# LeCoolStick-MainShield_v1.net
KiCad netlist of a schematic drawn in EAGLE
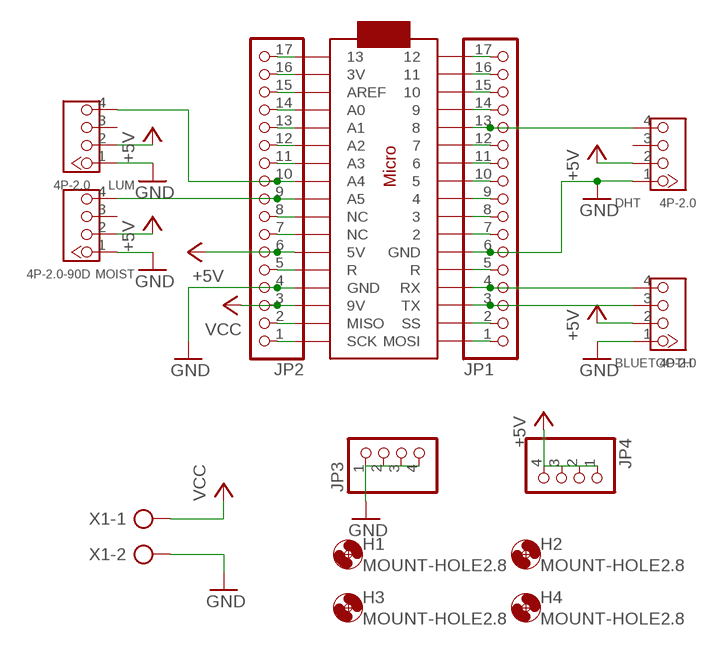
[diagram p0: schematic, sheet 1]

(export (version "E")
  (design (tool "Eeschema 10.0.6"))
  (components
    (comp (ref "BLUETOOTH")
      (value "4P-2.0")
      (footprint "eagle-import:HW4-2.0")
      (libsource (lib "eagle-import") (part "GROVE-CONNECTOR-DIP(4P-2.0)"))
    )
    (comp (ref "DHT")
      (value "4P-2.0")
      (footprint "eagle-import:HW4-2.0")
      (libsource (lib "eagle-import") (part "GROVE-CONNECTOR-DIP(4P-2.0)"))
    )
    (comp (ref "H1")
      (value "MOUNT-HOLE2.8")
      (footprint "eagle-import:2,8")
      (libsource (lib "eagle-import") (part "MOUNT-HOLE2.8"))
    )
    (comp (ref "H2")
      (value "MOUNT-HOLE2.8")
      (footprint "eagle-import:2,8")
      (libsource (lib "eagle-import") (part "MOUNT-HOLE2.8"))
    )
    (comp (ref "H3")
      (value "MOUNT-HOLE2.8")
      (footprint "eagle-import:2,8")
      (libsource (lib "eagle-import") (part "MOUNT-HOLE2.8"))
    )
    (comp (ref "H4")
      (value "MOUNT-HOLE2.8")
      (footprint "eagle-import:2,8")
      (libsource (lib "eagle-import") (part "MOUNT-HOLE2.8"))
    )
    (comp (ref "JP1")
      (value "PINHD-1X17")
      (footprint "eagle-import:1X17")
      (libsource (lib "eagle-import") (part "PINHD-1X17"))
    )
    (comp (ref "JP2")
      (value "PINHD-1X17")
      (footprint "eagle-import:1X17")
      (libsource (lib "eagle-import") (part "PINHD-1X17"))
    )
    (comp (ref "JP3")
      (value "PINHD-1X4")
      (footprint "eagle-import:1X04")
      (libsource (lib "eagle-import") (part "PINHD-1X4"))
    )
    (comp (ref "JP4")
      (value "PINHD-1X4")
      (footprint "eagle-import:1X04")
      (libsource (lib "eagle-import") (part "PINHD-1X4"))
    )
    (comp (ref "LUM")
      (value "4P-2.0")
      (footprint "eagle-import:HW4-2.0")
      (libsource (lib "eagle-import") (part "GROVE-CONNECTOR-DIP(4P-2.0)"))
    )
    (comp (ref "MOIST")
      (value "4P-2.0-90D")
      (footprint "eagle-import:HW4-2.0-90D")
      (libsource (lib "eagle-import") (part "GROVE-CONNECTOR-DIP-90D(4P-2.0)"))
    )
    (comp (ref "U$1")
      (value "ARDUINOMICRO")
      (footprint "eagle-import:ARDUINOMICRO")
      (libsource (lib "eagle-import") (part "ARDUINOMICRO"))
    )
    (comp (ref "X1")
      (value "AK500/2")
      (footprint "eagle-import:AK500_2")
      (libsource (lib "eagle-import") (part "AK500/2"))
    )
  )
  (nets
    (net (code "1") (name "+5V") (class "Default")
      (node (ref "BLUETOOTH") (pin "2") (pinfunction "2_2") (pintype "bidirectional"))
      (node (ref "DHT") (pin "2") (pinfunction "2_2") (pintype "bidirectional"))
      (node (ref "JP2") (pin "6") (pinfunction "6_6") (pintype "passive"))
      (node (ref "JP4") (pin "1") (pinfunction "1_1") (pintype "passive"))
      (node (ref "JP4") (pin "2") (pinfunction "2_2") (pintype "passive"))
      (node (ref "JP4") (pin "3") (pinfunction "3_3") (pintype "passive"))
      (node (ref "JP4") (pin "4") (pinfunction "4_4") (pintype "passive"))
      (node (ref "LUM") (pin "2") (pinfunction "2_2") (pintype "bidirectional"))
      (node (ref "MOIST") (pin "2") (pinfunction "2_2") (pintype "bidirectional"))
      (node (ref "U$1") (pin "P$23") (pinfunction "5V_P$23") (pintype "bidirectional"))
    )
    (net (code "2") (name "GND") (class "Default")
      (node (ref "BLUETOOTH") (pin "1") (pinfunction "1_1") (pintype "bidirectional"))
      (node (ref "DHT") (pin "1") (pinfunction "1_1") (pintype "bidirectional"))
      (node (ref "JP1") (pin "6") (pinfunction "6_6") (pintype "passive"))
      (node (ref "JP2") (pin "4") (pinfunction "4_4") (pintype "passive"))
      (node (ref "JP3") (pin "1") (pinfunction "1_1") (pintype "passive"))
      (node (ref "JP3") (pin "2") (pinfunction "2_2") (pintype "passive"))
      (node (ref "JP3") (pin "3") (pinfunction "3_3") (pintype "passive"))
      (node (ref "JP3") (pin "4") (pinfunction "4_4") (pintype "passive"))
      (node (ref "LUM") (pin "1") (pinfunction "1_1") (pintype "bidirectional"))
      (node (ref "MOIST") (pin "1") (pinfunction "1_1") (pintype "bidirectional"))
      (node (ref "U$1") (pin "P$12") (pinfunction "GND_P$12") (pintype "bidirectional"))
      (node (ref "U$1") (pin "P$21") (pinfunction "GND_P$21") (pintype "bidirectional"))
      (node (ref "X1") (pin "2") (pinfunction "KL_2") (pintype "passive"))
    )
    (net (code "3") (name "Net-(JP1-Pad5)") (class "Default")
      (node (ref "JP1") (pin "5") (pinfunction "5_5") (pintype "passive"))
      (node (ref "U$1") (pin "P$22") (pinfunction "R_P$22") (pintype "bidirectional"))
    )
    (net (code "4") (name "Net-(JP2-Pad5)") (class "Default")
      (node (ref "JP2") (pin "5") (pinfunction "5_5") (pintype "passive"))
      (node (ref "U$1") (pin "P$13") (pinfunction "R_P$13") (pintype "bidirectional"))
    )
    (net (code "5") (name "Net-(JP2-Pad7)") (class "Default")
      (node (ref "JP2") (pin "7") (pinfunction "7_7") (pintype "passive"))
      (node (ref "U$1") (pin "P$24") (pinfunction "NC_P$24") (pintype "bidirectional"))
    )
    (net (code "6") (name "Net-(JP2-Pad8)") (class "Default")
      (node (ref "JP2") (pin "8") (pinfunction "8_8") (pintype "passive"))
      (node (ref "U$1") (pin "P$25") (pinfunction "NC_P$25") (pintype "bidirectional"))
    )
    (net (code "7") (name "Net-(U$1-2)") (class "Default")
      (node (ref "JP1") (pin "7") (pinfunction "7_7") (pintype "passive"))
      (node (ref "U$1") (pin "P$11") (pinfunction "2_P$11") (pintype "bidirectional"))
    )
    (net (code "8") (name "Net-(U$1-3)") (class "Default")
      (node (ref "JP1") (pin "8") (pinfunction "8_8") (pintype "passive"))
      (node (ref "U$1") (pin "P$10") (pinfunction "3_P$10") (pintype "bidirectional"))
    )
    (net (code "9") (name "Net-(U$1-3V)") (class "Default")
      (node (ref "JP2") (pin "16") (pinfunction "16_16") (pintype "passive"))
      (node (ref "U$1") (pin "P$33") (pinfunction "3V_P$33") (pintype "bidirectional"))
    )
    (net (code "10") (name "Net-(U$1-4)") (class "Default")
      (node (ref "JP1") (pin "9") (pinfunction "9_9") (pintype "passive"))
      (node (ref "U$1") (pin "P$9") (pinfunction "4_P$9") (pintype "bidirectional"))
    )
    (net (code "11") (name "Net-(U$1-5)") (class "Default")
      (node (ref "JP1") (pin "10") (pinfunction "10_10") (pintype "passive"))
      (node (ref "U$1") (pin "P$8") (pinfunction "5_P$8") (pintype "bidirectional"))
    )
    (net (code "12") (name "Net-(U$1-6)") (class "Default")
      (node (ref "JP1") (pin "11") (pinfunction "11_11") (pintype "passive"))
      (node (ref "U$1") (pin "P$7") (pinfunction "6_P$7") (pintype "bidirectional"))
    )
    (net (code "13") (name "Net-(U$1-7)") (class "Default")
      (node (ref "JP1") (pin "12") (pinfunction "12_12") (pintype "passive"))
      (node (ref "U$1") (pin "P$6") (pinfunction "7_P$6") (pintype "bidirectional"))
    )
    (net (code "14") (name "Net-(U$1-8)") (class "Default")
      (node (ref "DHT") (pin "4") (pinfunction "4_4") (pintype "bidirectional"))
      (node (ref "JP1") (pin "13") (pinfunction "13_13") (pintype "passive"))
      (node (ref "U$1") (pin "P$5") (pinfunction "8_P$5") (pintype "bidirectional"))
    )
    (net (code "15") (name "Net-(U$1-9)") (class "Default")
      (node (ref "JP1") (pin "14") (pinfunction "14_14") (pintype "passive"))
      (node (ref "U$1") (pin "P$4") (pinfunction "9_P$4") (pintype "bidirectional"))
    )
    (net (code "16") (name "Net-(U$1-10)") (class "Default")
      (node (ref "JP1") (pin "15") (pinfunction "15_15") (pintype "passive"))
      (node (ref "U$1") (pin "P$3") (pinfunction "10_P$3") (pintype "bidirectional"))
    )
    (net (code "17") (name "Net-(U$1-11)") (class "Default")
      (node (ref "JP1") (pin "16") (pinfunction "16_16") (pintype "passive"))
      (node (ref "U$1") (pin "P$2") (pinfunction "11_P$2") (pintype "bidirectional"))
    )
    (net (code "18") (name "Net-(U$1-12)") (class "Default")
      (node (ref "JP1") (pin "17") (pinfunction "17_17") (pintype "passive"))
      (node (ref "U$1") (pin "P$1") (pinfunction "12_P$1") (pintype "bidirectional"))
    )
    (net (code "19") (name "Net-(U$1-13)") (class "Default")
      (node (ref "JP2") (pin "17") (pinfunction "17_17") (pintype "passive"))
      (node (ref "U$1") (pin "P$34") (pinfunction "13_P$34") (pintype "bidirectional"))
    )
    (net (code "20") (name "Net-(U$1-A0)") (class "Default")
      (node (ref "JP2") (pin "14") (pinfunction "14_14") (pintype "passive"))
      (node (ref "U$1") (pin "P$31") (pinfunction "A0_P$31") (pintype "bidirectional"))
    )
    (net (code "21") (name "Net-(U$1-A1)") (class "Default")
      (node (ref "JP2") (pin "13") (pinfunction "13_13") (pintype "passive"))
      (node (ref "U$1") (pin "P$30") (pinfunction "A1_P$30") (pintype "bidirectional"))
    )
    (net (code "22") (name "Net-(U$1-A2)") (class "Default")
      (node (ref "JP2") (pin "12") (pinfunction "12_12") (pintype "passive"))
      (node (ref "U$1") (pin "P$29") (pinfunction "A2_P$29") (pintype "bidirectional"))
    )
    (net (code "23") (name "Net-(U$1-A3)") (class "Default")
      (node (ref "JP2") (pin "11") (pinfunction "11_11") (pintype "passive"))
      (node (ref "U$1") (pin "P$28") (pinfunction "A3_P$28") (pintype "bidirectional"))
    )
    (net (code "24") (name "Net-(U$1-A4)") (class "Default")
      (node (ref "JP2") (pin "10") (pinfunction "10_10") (pintype "passive"))
      (node (ref "LUM") (pin "4") (pinfunction "4_4") (pintype "bidirectional"))
      (node (ref "U$1") (pin "P$27") (pinfunction "A4_P$27") (pintype "bidirectional"))
    )
    (net (code "25") (name "Net-(U$1-A5)") (class "Default")
      (node (ref "JP2") (pin "9") (pinfunction "9_9") (pintype "passive"))
      (node (ref "MOIST") (pin "4") (pinfunction "4_4") (pintype "bidirectional"))
      (node (ref "U$1") (pin "P$26") (pinfunction "A5_P$26") (pintype "bidirectional"))
    )
    (net (code "26") (name "Net-(U$1-AREF)") (class "Default")
      (node (ref "JP2") (pin "15") (pinfunction "15_15") (pintype "passive"))
      (node (ref "U$1") (pin "P$32") (pinfunction "AREF_P$32") (pintype "bidirectional"))
    )
    (net (code "27") (name "Net-(U$1-MISO)") (class "Default")
      (node (ref "JP2") (pin "2") (pinfunction "2_2") (pintype "passive"))
      (node (ref "U$1") (pin "P$19") (pinfunction "MISO_P$19") (pintype "bidirectional"))
    )
    (net (code "28") (name "Net-(U$1-MOSI)") (class "Default")
      (node (ref "JP1") (pin "1") (pinfunction "1_1") (pintype "passive"))
      (node (ref "U$1") (pin "P$17") (pinfunction "MOSI_P$17") (pintype "bidirectional"))
    )
    (net (code "29") (name "Net-(U$1-RX)") (class "Default")
      (node (ref "BLUETOOTH") (pin "4") (pinfunction "4_4") (pintype "bidirectional"))
      (node (ref "JP1") (pin "4") (pinfunction "4_4") (pintype "passive"))
      (node (ref "U$1") (pin "P$14") (pinfunction "RX_P$14") (pintype "bidirectional"))
    )
    (net (code "30") (name "Net-(U$1-SCK)") (class "Default")
      (node (ref "JP2") (pin "1") (pinfunction "1_1") (pintype "passive"))
      (node (ref "U$1") (pin "P$18") (pinfunction "SCK_P$18") (pintype "bidirectional"))
    )
    (net (code "31") (name "Net-(U$1-SS)") (class "Default")
      (node (ref "JP1") (pin "2") (pinfunction "2_2") (pintype "passive"))
      (node (ref "U$1") (pin "P$16") (pinfunction "SS_P$16") (pintype "bidirectional"))
    )
    (net (code "32") (name "Net-(U$1-TX)") (class "Default")
      (node (ref "BLUETOOTH") (pin "3") (pinfunction "3_3") (pintype "bidirectional"))
      (node (ref "JP1") (pin "3") (pinfunction "3_3") (pintype "passive"))
      (node (ref "U$1") (pin "P$15") (pinfunction "TX_P$15") (pintype "bidirectional"))
    )
    (net (code "33") (name "VCC") (class "Default")
      (node (ref "JP2") (pin "3") (pinfunction "3_3") (pintype "passive"))
      (node (ref "U$1") (pin "P$20") (pinfunction "9V_P$20") (pintype "bidirectional"))
      (node (ref "X1") (pin "1") (pinfunction "KL_1") (pintype "passive"))
    )
    (net (code "34") (name "unconnected-(DHT-Pad3)") (class "Default")
      (node (ref "DHT") (pin "3") (pinfunction "3_3") (pintype "bidirectional"))
    )
    (net (code "35") (name "unconnected-(LUM-Pad3)") (class "Default")
      (node (ref "LUM") (pin "3") (pinfunction "3_3") (pintype "bidirectional"))
    )
    (net (code "36") (name "unconnected-(MOIST-Pad3)") (class "Default")
      (node (ref "MOIST") (pin "3") (pinfunction "3_3") (pintype "bidirectional"))
    )
  )
)
